# Lora.net
KiCad netlist of a schematic drawn in Altium Designer
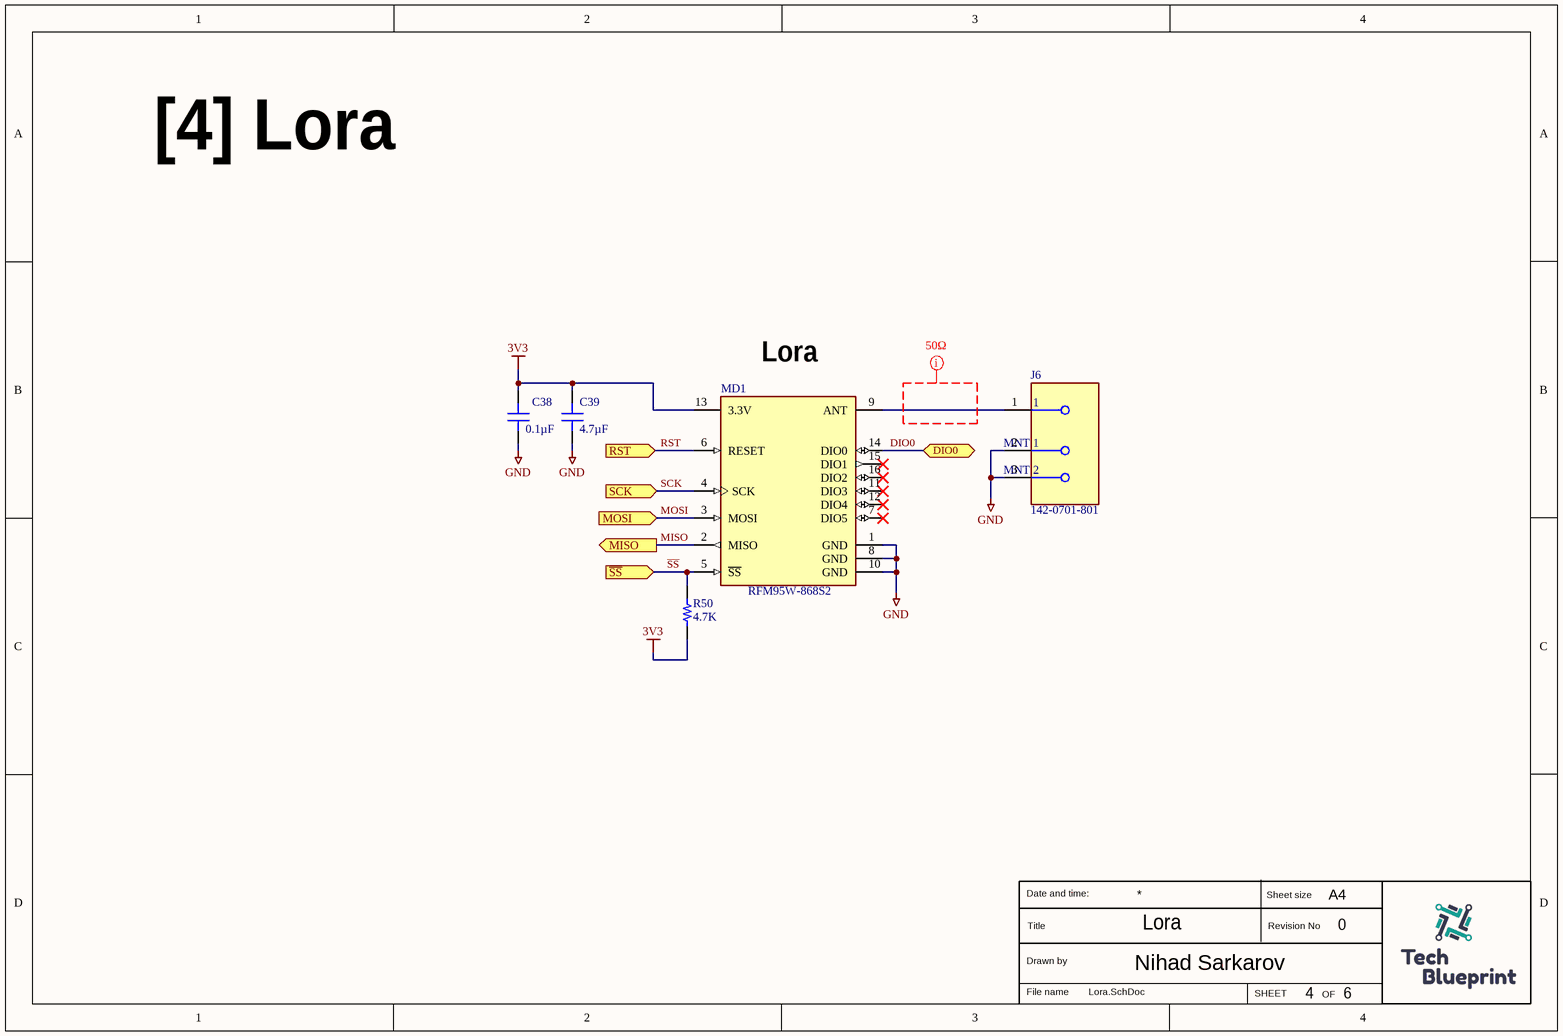
[diagram p0: Lora.SchDoc]

(export (version "E")
  (design (tool "Eeschema 10.0.6"))
  (components
    (comp (ref "C38")
      (value "0.1µF")
      (footprint "CAP 0805_2012")
      (description "CAP CER 0.1UF 25V X7R 0805")
      (fields
        (field (name "PART NUMBER") "08053C104KAT4A")
        (field (name "CAPACITANCE") "0.1µF")
        (field (name "MANUFACTURER") "AVX Corporation")
      )
      (libsource (lib "Celestial Altium Library - altium_library") (part "Capacitor"))
    )
    (comp (ref "C39")
      (value "4.7µF")
      (footprint "CAP 0805_2012")
      (description "CAP CER 4.7UF 10V X5R 0805")
      (fields
        (field (name "PART NUMBER") "0805ZD475KAT2A")
        (field (name "CAPACITANCE") "4.7µF")
        (field (name "MANUFACTURER") "AVX Corporation")
      )
      (libsource (lib "Celestial Altium Library - altium_library") (part "Capacitor"))
    )
    (comp (ref "J6")
      (value "142-0701-801")
      (footprint "FP-142-0701-801-MFG")
      (description "CONN SMA JACK STR 50OHM EDGE MNT")
      (libsource (lib "Altium Content Vault") (part "89929399afe843c8b6880c6cbd0f99a"))
    )
    (comp (ref "MD1")
      (value "RFM95W-868S2")
      (footprint "FP-RFM95W-868S2-MFG")
      (description "RX TXRX MODULE ISM < 1GHZ SMD")
      (libsource (lib "Altium Content Vault") (part "17626aa6fba47fab2b206b7c140802e"))
    )
    (comp (ref "R50")
      (value "4.7K")
      (footprint "KOA RES RK73 RN73 0603_1608")
      (description "RES 4.7K OHM 5% 1/10W 0603")
      (fields
        (field (name "PART NUMBER") "RK73B1JTTD472J")
        (field (name "MANUFACTURER") "KOA Speer Electronics, Inc.")
      )
      (libsource (lib "Celestial Altium Library - altium_library") (part "Resistor"))
    )
  )
  (nets
    (net (code "1") (name "/DIO0") (class "Default")
      (node (ref "MD1") (pin "14") (pinfunction "DIO0_14") (pintype "bidirectional"))
    )
    (net (code "2") (name "/MISO") (class "Default")
      (node (ref "MD1") (pin "2") (pinfunction "MISO_2") (pintype "output"))
    )
    (net (code "3") (name "/MOSI") (class "Default")
      (node (ref "MD1") (pin "3") (pinfunction "MOSI_3") (pintype "input"))
    )
    (net (code "4") (name "/RST") (class "Default")
      (node (ref "MD1") (pin "6") (pinfunction "RESET_6") (pintype "input"))
    )
    (net (code "5") (name "/SCK") (class "Default")
      (node (ref "MD1") (pin "4") (pinfunction "SCK_4") (pintype "input"))
    )
    (net (code "6") (name "/~{SS}") (class "Default")
      (node (ref "MD1") (pin "5") (pinfunction "~{SS}_5") (pintype "input"))
      (node (ref "R50") (pin "2") (pinfunction "2_2") (pintype "passive"))
    )
    (net (code "7") (name "3V3") (class "Default")
      (node (ref "C38") (pin "2") (pinfunction "2_2") (pintype "passive"))
      (node (ref "C39") (pin "2") (pinfunction "2_2") (pintype "passive"))
      (node (ref "MD1") (pin "13") (pinfunction "3.3V_13") (pintype "power_in"))
      (node (ref "R50") (pin "1") (pinfunction "1_1") (pintype "passive"))
    )
    (net (code "8") (name "GND") (class "Default")
      (node (ref "C38") (pin "1") (pinfunction "1_1") (pintype "passive"))
      (node (ref "C39") (pin "1") (pinfunction "1_1") (pintype "passive"))
      (node (ref "J6") (pin "2") (pinfunction "MNT_1_2") (pintype "passive"))
      (node (ref "J6") (pin "3") (pinfunction "MNT_2_3") (pintype "passive"))
      (node (ref "MD1") (pin "1") (pinfunction "GND_1") (pintype "power_in"))
      (node (ref "MD1") (pin "10") (pinfunction "GND_10") (pintype "power_in"))
      (node (ref "MD1") (pin "8") (pinfunction "GND_8") (pintype "power_in"))
    )
    (net (code "9") (name "Net-(MD1-ANT)") (class "Default")
      (node (ref "J6") (pin "1") (pinfunction "1_1") (pintype "passive"))
      (node (ref "MD1") (pin "9") (pinfunction "ANT_9") (pintype "passive"))
    )
    (net (code "10") (name "unconnected-(MD1-DIO1-Pad15)") (class "Default")
      (node (ref "MD1") (pin "15") (pinfunction "DIO1_15") (pintype "output+no_connect"))
    )
    (net (code "11") (name "unconnected-(MD1-DIO2-Pad16)") (class "Default")
      (node (ref "MD1") (pin "16") (pinfunction "DIO2_16") (pintype "bidirectional+no_connect"))
    )
    (net (code "12") (name "unconnected-(MD1-DIO3-Pad11)") (class "Default")
      (node (ref "MD1") (pin "11") (pinfunction "DIO3_11") (pintype "bidirectional+no_connect"))
    )
    (net (code "13") (name "unconnected-(MD1-DIO4-Pad12)") (class "Default")
      (node (ref "MD1") (pin "12") (pinfunction "DIO4_12") (pintype "bidirectional+no_connect"))
    )
    (net (code "14") (name "unconnected-(MD1-DIO5-Pad7)") (class "Default")
      (node (ref "MD1") (pin "7") (pinfunction "DIO5_7") (pintype "bidirectional+no_connect"))
    )
  )
)
